# wagband_schematic.net
KiCad netlist of a schematic drawn in EAGLE
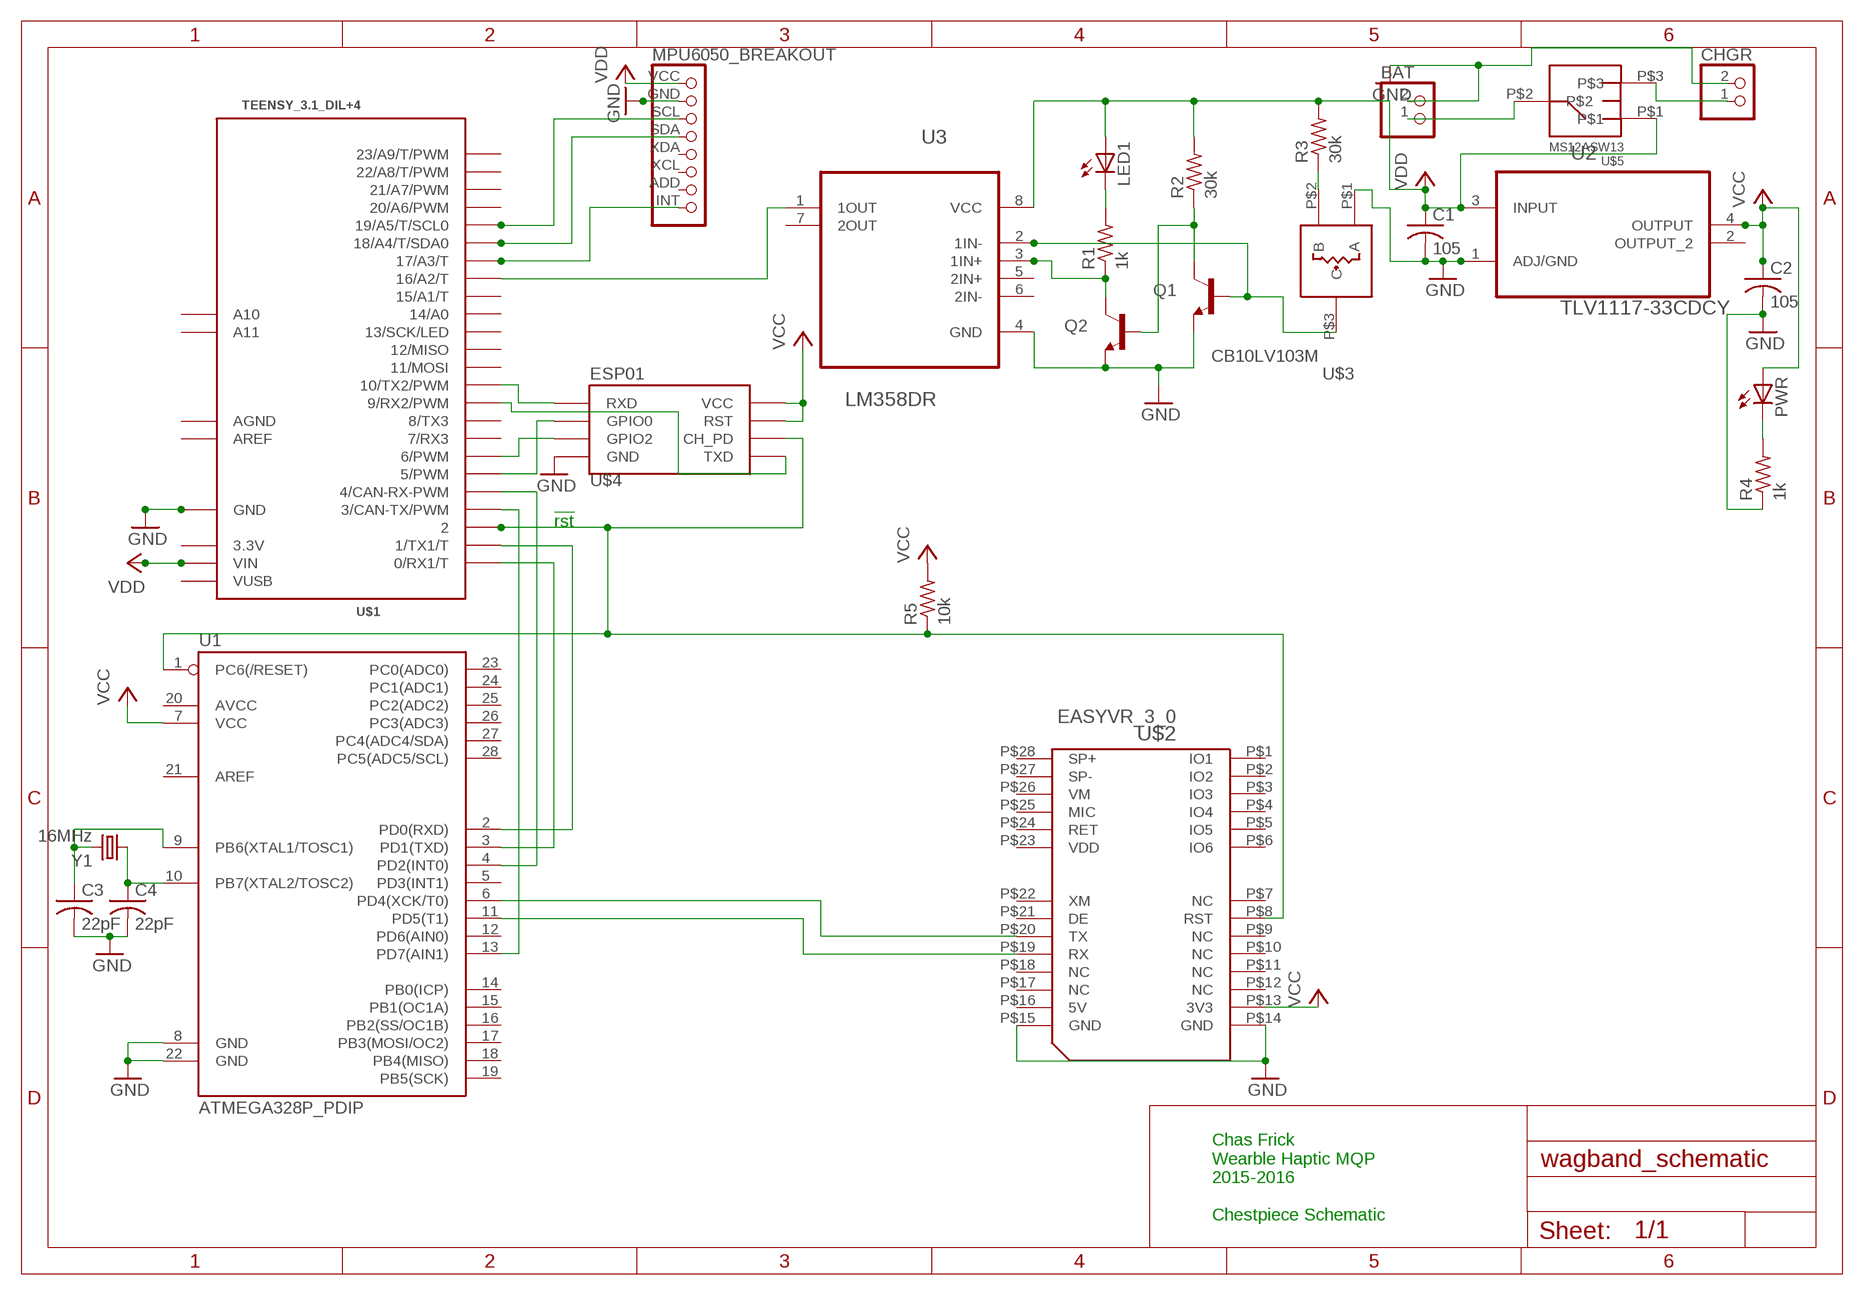
[diagram p0: schematic, sheet 1]

(export (version "E")
  (design (tool "Eeschema 10.0.6"))
  (components
    (comp (ref "BAT")
      (value "JST_2PIN-THM-RA")
      (footprint "eagle-import:JST-PH-2-THM-RA")
      (libsource (lib "eagle-import") (part "JST_2PIN-THM-RA"))
    )
    (comp (ref "C1")
      (value "105")
      (footprint "eagle-import:C0805K")
      (libsource (lib "eagle-import") (part "resistor_C-USC0805K"))
    )
    (comp (ref "C2")
      (value "105")
      (footprint "eagle-import:C0805K")
      (libsource (lib "eagle-import") (part "resistor_C-USC0805K"))
    )
    (comp (ref "C3")
      (value "22pF")
      (footprint "eagle-import:C1206K")
      (libsource (lib "eagle-import") (part "C-USC1206K"))
    )
    (comp (ref "C4")
      (value "22pF")
      (footprint "eagle-import:C1206K")
      (libsource (lib "eagle-import") (part "C-USC1206K"))
    )
    (comp (ref "CHGR")
      (value "JST_2PIN-THM-RA")
      (footprint "eagle-import:JST-PH-2-THM-RA")
      (libsource (lib "eagle-import") (part "JST_2PIN-THM-RA"))
    )
    (comp (ref "LED1")
      (value "LED5MM")
      (footprint "eagle-import:LED5MM")
      (libsource (lib "eagle-import") (part "LED5MM"))
    )
    (comp (ref "MPU6050_BREAKOUT")
      (value "MPU6050_BREAKOUT")
      (footprint "eagle-import:MPU6050")
      (libsource (lib "eagle-import") (part "MPU6050_BREAKOUT"))
    )
    (comp (ref "PWR")
      (value "LED5MM")
      (footprint "eagle-import:LED5MM")
      (libsource (lib "eagle-import") (part "LED5MM"))
    )
    (comp (ref "Q1")
      (value "TRANSISTOR_NPNMMBT3904")
      (footprint "eagle-import:SOT-23")
      (libsource (lib "eagle-import") (part "TRANSISTOR_NPNMMBT3904"))
    )
    (comp (ref "Q2")
      (value "TRANSISTOR_NPNMMBT3904")
      (footprint "eagle-import:SOT-23")
      (libsource (lib "eagle-import") (part "TRANSISTOR_NPNMMBT3904"))
    )
    (comp (ref "R1")
      (value "1k")
      (footprint "eagle-import:R1206")
      (libsource (lib "eagle-import") (part "R-US_R1206"))
    )
    (comp (ref "R2")
      (value "30k")
      (footprint "eagle-import:R1206")
      (libsource (lib "eagle-import") (part "R-US_R1206"))
    )
    (comp (ref "R3")
      (value "30k")
      (footprint "eagle-import:R1206")
      (libsource (lib "eagle-import") (part "R-US_R1206"))
    )
    (comp (ref "R4")
      (value "1k")
      (footprint "eagle-import:R1206")
      (libsource (lib "eagle-import") (part "R-US_R1206"))
    )
    (comp (ref "R5")
      (value "10k")
      (footprint "eagle-import:R1206")
      (libsource (lib "eagle-import") (part "R-US_R1206"))
    )
    (comp (ref "U$1")
      (value "TEENSY_3.1_DIL+4")
      (footprint "eagle-import:TEENSY3-DIL+4")
      (libsource (lib "eagle-import") (part "TEENSY_3.1_DIL+4"))
    )
    (comp (ref "U$2")
      (value "EASYVR_3_0")
      (footprint "eagle-import:EASYVR_3_0")
      (libsource (lib "eagle-import") (part "EASYVR_3_0"))
    )
    (comp (ref "U$3")
      (value "CB10LV103M")
      (footprint "eagle-import:CB10")
      (libsource (lib "eagle-import") (part "CB10LV103M"))
    )
    (comp (ref "U$4")
      (value "ESP01")
      (footprint "eagle-import:ESP01")
      (libsource (lib "eagle-import") (part "ESP01"))
    )
    (comp (ref "U$5")
      (value "MS12ASW13")
      (footprint "eagle-import:SPDT")
      (libsource (lib "eagle-import") (part "MS12ASW13"))
    )
    (comp (ref "U1")
      (value "ATMEGA328P_PDIP")
      (footprint "eagle-import:DIL28-3")
      (libsource (lib "eagle-import") (part "ATMEGA328P_PDIP"))
    )
    (comp (ref "U2")
      (value "TLV1117-33CDCY")
      (footprint "eagle-import:SOT230P700X180-4N")
      (libsource (lib "eagle-import") (part "TLV1117-33CDCY"))
    )
    (comp (ref "U3")
      (value "LM358DR")
      (footprint "eagle-import:SOIC127P600X175-8N")
      (libsource (lib "eagle-import") (part "LM358DR"))
    )
    (comp (ref "Y1")
      (value "16MHz")
      (footprint "eagle-import:HC49UP")
      (libsource (lib "eagle-import") (part "CRYSTALSMD"))
    )
  )
  (nets
    (net (code "1") (name "/3.3V") (class "Default")
      (node (ref "U$1") (pin "3.3V") (pinfunction "3.3V_3.3V") (pintype "power_in"))
    )
    (net (code "2") (name "/AGND") (class "Default")
      (node (ref "U$1") (pin "AGND") (pinfunction "AGND_AGND") (pintype "power_in"))
    )
    (net (code "3") (name "/AREF") (class "Default")
      (node (ref "U$1") (pin "AREF") (pinfunction "AREF_AREF") (pintype "power_in"))
    )
    (net (code "4") (name "/VUSB") (class "Default")
      (node (ref "U$1") (pin "VUSB") (pinfunction "VUSB_VUSB") (pintype "power_in"))
    )
    (net (code "5") (name "GND") (class "Default")
      (node (ref "BAT") (pin "2") (pinfunction "1_2") (pintype "passive"))
      (node (ref "C1") (pin "2") (pinfunction "2_2") (pintype "passive"))
      (node (ref "C2") (pin "2") (pinfunction "2_2") (pintype "passive"))
      (node (ref "C3") (pin "2") (pinfunction "2_2") (pintype "passive"))
      (node (ref "C4") (pin "2") (pinfunction "2_2") (pintype "passive"))
      (node (ref "CHGR") (pin "2") (pinfunction "1_2") (pintype "passive"))
      (node (ref "MPU6050_BREAKOUT") (pin "GND") (pinfunction "GND_GND") (pintype "passive"))
      (node (ref "Q1") (pin "2") (pinfunction "E_2") (pintype "passive"))
      (node (ref "Q2") (pin "2") (pinfunction "E_2") (pintype "passive"))
      (node (ref "R4") (pin "1") (pinfunction "1_1") (pintype "passive"))
      (node (ref "U$1") (pin "GND") (pinfunction "GND_GND") (pintype "power_in"))
      (node (ref "U$2") (pin "P$14") (pinfunction "GND_P$14") (pintype "power_in"))
      (node (ref "U$2") (pin "P$15") (pinfunction "GND_P$15") (pintype "power_in"))
      (node (ref "U$3") (pin "P$1") (pinfunction "A_P$1") (pintype "bidirectional"))
      (node (ref "U$4") (pin "GND") (pinfunction "GND_GND") (pintype "bidirectional"))
      (node (ref "U1") (pin "22") (pinfunction "GND_22") (pintype "bidirectional"))
      (node (ref "U1") (pin "8") (pinfunction "GND_8") (pintype "bidirectional"))
      (node (ref "U2") (pin "1") (pinfunction "ADJ/GND_1") (pintype "input"))
      (node (ref "U3") (pin "4") (pinfunction "GND_4") (pintype "passive"))
    )
    (net (code "6") (name "Net-(BAT-2)") (class "Default")
      (node (ref "BAT") (pin "1") (pinfunction "2_1") (pintype "passive"))
      (node (ref "U$5") (pin "P$2") (pinfunction "P$2_P$2") (pintype "bidirectional"))
    )
    (net (code "7") (name "Net-(CHGR-2)") (class "Default")
      (node (ref "CHGR") (pin "1") (pinfunction "2_1") (pintype "passive"))
      (node (ref "U$5") (pin "P$3") (pinfunction "P$3_P$3") (pintype "bidirectional"))
    )
    (net (code "8") (name "Net-(LED1-C)") (class "Default")
      (node (ref "LED1") (pin "K") (pinfunction "C_K") (pintype "passive"))
      (node (ref "R1") (pin "2") (pinfunction "2_2") (pintype "passive"))
    )
    (net (code "9") (name "Net-(PWR-C)") (class "Default")
      (node (ref "PWR") (pin "K") (pinfunction "C_K") (pintype "passive"))
      (node (ref "R4") (pin "2") (pinfunction "2_2") (pintype "passive"))
    )
    (net (code "10") (name "Net-(Q1-B)") (class "Default")
      (node (ref "Q1") (pin "1") (pinfunction "B_1") (pintype "passive"))
      (node (ref "U$3") (pin "P$3") (pinfunction "C_P$3") (pintype "bidirectional"))
      (node (ref "U3") (pin "2") (pinfunction "1IN-_2") (pintype "input"))
    )
    (net (code "11") (name "Net-(Q1-C)") (class "Default")
      (node (ref "Q1") (pin "3") (pinfunction "C_3") (pintype "passive"))
      (node (ref "Q2") (pin "1") (pinfunction "B_1") (pintype "passive"))
      (node (ref "R2") (pin "1") (pinfunction "1_1") (pintype "passive"))
    )
    (net (code "12") (name "Net-(Q2-C)") (class "Default")
      (node (ref "Q2") (pin "3") (pinfunction "C_3") (pintype "passive"))
      (node (ref "R1") (pin "1") (pinfunction "1_1") (pintype "passive"))
      (node (ref "U3") (pin "3") (pinfunction "1IN+_3") (pintype "input"))
    )
    (net (code "13") (name "Net-(U$1-0{slash}RX1{slash}T)") (class "Default")
      (node (ref "U$1") (pin "0") (pinfunction "0/RX1/T_0") (pintype "bidirectional"))
      (node (ref "U1") (pin "3") (pinfunction "PD1(TXD)_3") (pintype "bidirectional"))
    )
    (net (code "14") (name "Net-(U$1-1{slash}TX1{slash}T)") (class "Default")
      (node (ref "U$1") (pin "1") (pinfunction "1/TX1/T_1") (pintype "bidirectional"))
      (node (ref "U1") (pin "2") (pinfunction "PD0(RXD)_2") (pintype "bidirectional"))
    )
    (net (code "15") (name "Net-(U$1-3{slash}CAN-TX{slash}PWM)") (class "Default")
      (node (ref "U$1") (pin "3") (pinfunction "3/CAN-TX/PWM_3") (pintype "bidirectional"))
      (node (ref "U1") (pin "13") (pinfunction "PD7(AIN1)_13") (pintype "bidirectional"))
    )
    (net (code "16") (name "Net-(U$1-4{slash}CAN-RX-PWM)") (class "Default")
      (node (ref "U$1") (pin "4") (pinfunction "4/CAN-RX-PWM_4") (pintype "bidirectional"))
      (node (ref "U1") (pin "4") (pinfunction "PD2(INT0)_4") (pintype "bidirectional"))
    )
    (net (code "17") (name "Net-(U$1-5{slash}PWM)") (class "Default")
      (node (ref "U$1") (pin "5") (pinfunction "5/PWM_5") (pintype "bidirectional"))
      (node (ref "U$4") (pin "GPIO0") (pinfunction "GPIO0_GPIO0") (pintype "bidirectional"))
    )
    (net (code "18") (name "Net-(U$1-6{slash}PWM)") (class "Default")
      (node (ref "U$1") (pin "6") (pinfunction "6/PWM_6") (pintype "bidirectional"))
      (node (ref "U$4") (pin "GPIO2") (pinfunction "GPIO2_GPIO2") (pintype "bidirectional"))
    )
    (net (code "19") (name "Net-(U$1-9{slash}RX2{slash}PWM)") (class "Default")
      (node (ref "U$1") (pin "9") (pinfunction "9/RX2/PWM_9") (pintype "bidirectional"))
      (node (ref "U$4") (pin "TX") (pinfunction "TXD_TX") (pintype "bidirectional"))
    )
    (net (code "20") (name "Net-(U$1-10{slash}TX2{slash}PWM)") (class "Default")
      (node (ref "U$1") (pin "10") (pinfunction "10/TX2/PWM_10") (pintype "bidirectional"))
      (node (ref "U$4") (pin "RX") (pinfunction "RXD_RX") (pintype "bidirectional"))
    )
    (net (code "21") (name "Net-(U$1-16{slash}A2{slash}T)") (class "Default")
      (node (ref "U$1") (pin "16/A2") (pinfunction "16/A2/T_16/A2") (pintype "bidirectional"))
      (node (ref "U3") (pin "1") (pinfunction "1OUT_1") (pintype "output"))
    )
    (net (code "22") (name "Net-(U$1-17{slash}A3{slash}T)") (class "Default")
      (node (ref "MPU6050_BREAKOUT") (pin "INT") (pinfunction "INT_INT") (pintype "passive"))
      (node (ref "U$1") (pin "17/A3") (pinfunction "17/A3/T_17/A3") (pintype "bidirectional"))
    )
    (net (code "23") (name "Net-(U$1-18{slash}A4{slash}T{slash}SDA0)") (class "Default")
      (node (ref "MPU6050_BREAKOUT") (pin "SDA") (pinfunction "SDA_SDA") (pintype "passive"))
      (node (ref "U$1") (pin "18/A4") (pinfunction "18/A4/T/SDA0_18/A4") (pintype "bidirectional"))
    )
    (net (code "24") (name "Net-(U$1-19{slash}A5{slash}T{slash}SCL0)") (class "Default")
      (node (ref "MPU6050_BREAKOUT") (pin "SCL") (pinfunction "SCL_SCL") (pintype "passive"))
      (node (ref "U$1") (pin "19/A5") (pinfunction "19/A5/T/SCL0_19/A5") (pintype "bidirectional"))
    )
    (net (code "25") (name "Net-(U$2-RST)") (class "Default")
      (node (ref "R5") (pin "1") (pinfunction "1_1") (pintype "passive"))
      (node (ref "U$1") (pin "2") (pinfunction "2_2") (pintype "bidirectional"))
      (node (ref "U$2") (pin "P$8") (pinfunction "RST_P$8") (pintype "input"))
      (node (ref "U$4") (pin "CH_PD") (pinfunction "CH_PD_CH_PD") (pintype "bidirectional"))
      (node (ref "U1") (pin "1") (pinfunction "PC6(/RESET)_1") (pintype "bidirectional"))
    )
    (net (code "26") (name "Net-(U$2-RX)") (class "Default")
      (node (ref "U$2") (pin "P$19") (pinfunction "RX_P$19") (pintype "input"))
      (node (ref "U1") (pin "11") (pinfunction "PD5(T1)_11") (pintype "bidirectional"))
    )
    (net (code "27") (name "Net-(U$2-TX)") (class "Default")
      (node (ref "U$2") (pin "P$20") (pinfunction "TX_P$20") (pintype "output"))
      (node (ref "U1") (pin "6") (pinfunction "PD4(XCK/T0)_6") (pintype "bidirectional"))
    )
    (net (code "28") (name "Net-(U$3-B)") (class "Default")
      (node (ref "R3") (pin "1") (pinfunction "1_1") (pintype "passive"))
      (node (ref "U$3") (pin "P$2") (pinfunction "B_P$2") (pintype "bidirectional"))
    )
    (net (code "29") (name "Net-(U1-PB6(XTAL1{slash}TOSC1))") (class "Default")
      (node (ref "C3") (pin "1") (pinfunction "1_1") (pintype "passive"))
      (node (ref "U1") (pin "9") (pinfunction "PB6(XTAL1/TOSC1)_9") (pintype "bidirectional"))
      (node (ref "Y1") (pin "2") (pinfunction "2_2") (pintype "passive"))
    )
    (net (code "30") (name "Net-(U1-PB7(XTAL2{slash}TOSC2))") (class "Default")
      (node (ref "C4") (pin "1") (pinfunction "1_1") (pintype "passive"))
      (node (ref "U1") (pin "10") (pinfunction "PB7(XTAL2/TOSC2)_10") (pintype "bidirectional"))
      (node (ref "Y1") (pin "1") (pinfunction "1_1") (pintype "passive"))
    )
    (net (code "31") (name "VCC") (class "Default")
      (node (ref "C1") (pin "1") (pinfunction "1_1") (pintype "passive"))
      (node (ref "C2") (pin "1") (pinfunction "1_1") (pintype "passive"))
      (node (ref "LED1") (pin "A") (pinfunction "A_A") (pintype "passive"))
      (node (ref "MPU6050_BREAKOUT") (pin "VCC") (pinfunction "VCC_VCC") (pintype "passive"))
      (node (ref "PWR") (pin "A") (pinfunction "A_A") (pintype "passive"))
      (node (ref "R2") (pin "2") (pinfunction "2_2") (pintype "passive"))
      (node (ref "R3") (pin "2") (pinfunction "2_2") (pintype "passive"))
      (node (ref "R5") (pin "2") (pinfunction "2_2") (pintype "passive"))
      (node (ref "U$1") (pin "VIN") (pinfunction "VIN_VIN") (pintype "power_in"))
      (node (ref "U$2") (pin "P$13") (pinfunction "3V3_P$13") (pintype "power_in"))
      (node (ref "U$4") (pin "RST") (pinfunction "RST_RST") (pintype "bidirectional"))
      (node (ref "U$4") (pin "VCC") (pinfunction "VCC_VCC") (pintype "bidirectional"))
      (node (ref "U$5") (pin "P$1") (pinfunction "P$1_P$1") (pintype "bidirectional"))
      (node (ref "U1") (pin "7") (pinfunction "VCC_7") (pintype "bidirectional"))
      (node (ref "U2") (pin "3") (pinfunction "INPUT_3") (pintype "input"))
      (node (ref "U2") (pin "4") (pinfunction "OUTPUT_4") (pintype "output"))
      (node (ref "U3") (pin "8") (pinfunction "VCC_8") (pintype "power_in"))
    )
    (net (code "32") (name "unconnected-(MPU6050_BREAKOUT-PadADD)") (class "Default")
      (node (ref "MPU6050_BREAKOUT") (pin "ADD") (pinfunction "ADD_ADD") (pintype "passive"))
    )
    (net (code "33") (name "unconnected-(MPU6050_BREAKOUT-PadXCL)") (class "Default")
      (node (ref "MPU6050_BREAKOUT") (pin "XCL") (pinfunction "XCL_XCL") (pintype "passive"))
    )
    (net (code "34") (name "unconnected-(MPU6050_BREAKOUT-PadXDA)") (class "Default")
      (node (ref "MPU6050_BREAKOUT") (pin "XDA") (pinfunction "XDA_XDA") (pintype "passive"))
    )
    (net (code "35") (name "unconnected-(U$1-7{slash}RX3-Pad7)") (class "Default")
      (node (ref "U$1") (pin "7") (pinfunction "7/RX3_7") (pintype "bidirectional"))
    )
    (net (code "36") (name "unconnected-(U$1-8{slash}TX3-Pad8)") (class "Default")
      (node (ref "U$1") (pin "8") (pinfunction "8/TX3_8") (pintype "bidirectional"))
    )
    (net (code "37") (name "unconnected-(U$1-11{slash}MOSI-Pad11)") (class "Default")
      (node (ref "U$1") (pin "11") (pinfunction "11/MOSI_11") (pintype "bidirectional"))
    )
    (net (code "38") (name "unconnected-(U$1-12{slash}MISO-Pad12)") (class "Default")
      (node (ref "U$1") (pin "12") (pinfunction "12/MISO_12") (pintype "bidirectional"))
    )
    (net (code "39") (name "unconnected-(U$1-13{slash}SCK{slash}LED-Pad13)") (class "Default")
      (node (ref "U$1") (pin "13") (pinfunction "13/SCK/LED_13") (pintype "bidirectional"))
    )
    (net (code "40") (name "unconnected-(U$1-15{slash}A1{slash}T-Pad15{slash}A1)") (class "Default")
      (node (ref "U$1") (pin "15/A1") (pinfunction "15/A1/T_15/A1") (pintype "bidirectional"))
    )
    (net (code "41") (name "unconnected-(U$1-20{slash}A6{slash}PWM-Pad20{slash}A6)") (class "Default")
      (node (ref "U$1") (pin "20/A6") (pinfunction "20/A6/PWM_20/A6") (pintype "bidirectional"))
    )
    (net (code "42") (name "unconnected-(U$1-21{slash}A7{slash}PWM-Pad21{slash}A7)") (class "Default")
      (node (ref "U$1") (pin "21/A7") (pinfunction "21/A7/PWM_21/A7") (pintype "bidirectional"))
    )
    (net (code "43") (name "unconnected-(U$1-22{slash}A8{slash}T{slash}PWM-Pad22{slash}A8)") (class "Default")
      (node (ref "U$1") (pin "22/A8") (pinfunction "22/A8/T/PWM_22/A8") (pintype "bidirectional"))
    )
    (net (code "44") (name "unconnected-(U$1-23{slash}A9{slash}T{slash}PWM-Pad23{slash}A9)") (class "Default")
      (node (ref "U$1") (pin "23/A9") (pinfunction "23/A9/T/PWM_23/A9") (pintype "bidirectional"))
    )
    (net (code "45") (name "unconnected-(U$1-Pad14{slash}A0)") (class "Default")
      (node (ref "U$1") (pin "14/A0") (pinfunction "14/A0_14/A0") (pintype "bidirectional"))
    )
    (net (code "46") (name "unconnected-(U$1-PadA10)") (class "Default")
      (node (ref "U$1") (pin "A10") (pinfunction "A10_A10") (pintype "bidirectional"))
    )
    (net (code "47") (name "unconnected-(U$1-PadA11)") (class "Default")
      (node (ref "U$1") (pin "A11") (pinfunction "A11_A11") (pintype "bidirectional"))
    )
    (net (code "48") (name "unconnected-(U$2-5V-PadP$16)") (class "Default")
      (node (ref "U$2") (pin "P$16") (pinfunction "5V_P$16") (pintype "power_in"))
    )
    (net (code "49") (name "unconnected-(U$2-DE-PadP$21)") (class "Default")
      (node (ref "U$2") (pin "P$21") (pinfunction "DE_P$21") (pintype "bidirectional"))
    )
    (net (code "50") (name "unconnected-(U$2-IO1-PadP$1)") (class "Default")
      (node (ref "U$2") (pin "P$1") (pinfunction "IO1_P$1") (pintype "bidirectional"))
    )
    (net (code "51") (name "unconnected-(U$2-IO2-PadP$2)") (class "Default")
      (node (ref "U$2") (pin "P$2") (pinfunction "IO2_P$2") (pintype "bidirectional"))
    )
    (net (code "52") (name "unconnected-(U$2-IO3-PadP$3)") (class "Default")
      (node (ref "U$2") (pin "P$3") (pinfunction "IO3_P$3") (pintype "bidirectional"))
    )
    (net (code "53") (name "unconnected-(U$2-IO4-PadP$4)") (class "Default")
      (node (ref "U$2") (pin "P$4") (pinfunction "IO4_P$4") (pintype "bidirectional"))
    )
    (net (code "54") (name "unconnected-(U$2-IO5-PadP$5)") (class "Default")
      (node (ref "U$2") (pin "P$5") (pinfunction "IO5_P$5") (pintype "bidirectional"))
    )
    (net (code "55") (name "unconnected-(U$2-IO6-PadP$6)") (class "Default")
      (node (ref "U$2") (pin "P$6") (pinfunction "IO6_P$6") (pintype "bidirectional"))
    )
    (net (code "56") (name "unconnected-(U$2-MIC-PadP$25)") (class "Default")
      (node (ref "U$2") (pin "P$25") (pinfunction "MIC_P$25") (pintype "bidirectional"))
    )
    (net (code "57") (name "unconnected-(U$2-NC-PadP$7)") (class "Default")
      (node (ref "U$2") (pin "P$7") (pinfunction "NC_P$7") (pintype "no_connect"))
    )
    (net (code "58") (name "unconnected-(U$2-NC-PadP$9)") (class "Default")
      (node (ref "U$2") (pin "P$9") (pinfunction "NC_P$9") (pintype "no_connect"))
    )
    (net (code "59") (name "unconnected-(U$2-NC-PadP$10)") (class "Default")
      (node (ref "U$2") (pin "P$10") (pinfunction "NC_P$10") (pintype "no_connect"))
    )
    (net (code "60") (name "unconnected-(U$2-NC-PadP$11)") (class "Default")
      (node (ref "U$2") (pin "P$11") (pinfunction "NC_P$11") (pintype "no_connect"))
    )
    (net (code "61") (name "unconnected-(U$2-NC-PadP$12)") (class "Default")
      (node (ref "U$2") (pin "P$12") (pinfunction "NC_P$12") (pintype "no_connect"))
    )
    (net (code "62") (name "unconnected-(U$2-NC-PadP$17)") (class "Default")
      (node (ref "U$2") (pin "P$17") (pinfunction "NC_P$17") (pintype "no_connect"))
    )
    (net (code "63") (name "unconnected-(U$2-NC-PadP$18)") (class "Default")
      (node (ref "U$2") (pin "P$18") (pinfunction "NC_P$18") (pintype "no_connect"))
    )
    (net (code "64") (name "unconnected-(U$2-RET-PadP$24)") (class "Default")
      (node (ref "U$2") (pin "P$24") (pinfunction "RET_P$24") (pintype "bidirectional"))
    )
    (net (code "65") (name "unconnected-(U$2-SP+-PadP$28)") (class "Default")
      (node (ref "U$2") (pin "P$28") (pinfunction "SP+_P$28") (pintype "bidirectional"))
    )
    (net (code "66") (name "unconnected-(U$2-SP--PadP$27)") (class "Default")
      (node (ref "U$2") (pin "P$27") (pinfunction "SP-_P$27") (pintype "bidirectional"))
    )
    (net (code "67") (name "unconnected-(U$2-VDD-PadP$23)") (class "Default")
      (node (ref "U$2") (pin "P$23") (pinfunction "VDD_P$23") (pintype "power_in"))
    )
    (net (code "68") (name "unconnected-(U$2-VM-PadP$26)") (class "Default")
      (node (ref "U$2") (pin "P$26") (pinfunction "VM_P$26") (pintype "bidirectional"))
    )
    (net (code "69") (name "unconnected-(U$2-XM-PadP$22)") (class "Default")
      (node (ref "U$2") (pin "P$22") (pinfunction "XM_P$22") (pintype "bidirectional"))
    )
    (net (code "70") (name "unconnected-(U1-AREF-Pad21)") (class "Default")
      (node (ref "U1") (pin "21") (pinfunction "AREF_21") (pintype "bidirectional"))
    )
    (net (code "71") (name "unconnected-(U1-AVCC-Pad20)") (class "Default")
      (node (ref "U1") (pin "20") (pinfunction "AVCC_20") (pintype "bidirectional"))
    )
    (net (code "72") (name "unconnected-(U1-PB0(ICP)-Pad14)") (class "Default")
      (node (ref "U1") (pin "14") (pinfunction "PB0(ICP)_14") (pintype "bidirectional"))
    )
    (net (code "73") (name "unconnected-(U1-PB1(OC1A)-Pad15)") (class "Default")
      (node (ref "U1") (pin "15") (pinfunction "PB1(OC1A)_15") (pintype "bidirectional"))
    )
    (net (code "74") (name "unconnected-(U1-PB2(SS{slash}OC1B)-Pad16)") (class "Default")
      (node (ref "U1") (pin "16") (pinfunction "PB2(SS/OC1B)_16") (pintype "bidirectional"))
    )
    (net (code "75") (name "unconnected-(U1-PB3(MOSI{slash}OC2)-Pad17)") (class "Default")
      (node (ref "U1") (pin "17") (pinfunction "PB3(MOSI/OC2)_17") (pintype "bidirectional"))
    )
    (net (code "76") (name "unconnected-(U1-PB4(MISO)-Pad18)") (class "Default")
      (node (ref "U1") (pin "18") (pinfunction "PB4(MISO)_18") (pintype "bidirectional"))
    )
    (net (code "77") (name "unconnected-(U1-PB5(SCK)-Pad19)") (class "Default")
      (node (ref "U1") (pin "19") (pinfunction "PB5(SCK)_19") (pintype "bidirectional"))
    )
    (net (code "78") (name "unconnected-(U1-PC0(ADC0)-Pad23)") (class "Default")
      (node (ref "U1") (pin "23") (pinfunction "PC0(ADC0)_23") (pintype "bidirectional"))
    )
    (net (code "79") (name "unconnected-(U1-PC1(ADC1)-Pad24)") (class "Default")
      (node (ref "U1") (pin "24") (pinfunction "PC1(ADC1)_24") (pintype "bidirectional"))
    )
    (net (code "80") (name "unconnected-(U1-PC2(ADC2)-Pad25)") (class "Default")
      (node (ref "U1") (pin "25") (pinfunction "PC2(ADC2)_25") (pintype "bidirectional"))
    )
    (net (code "81") (name "unconnected-(U1-PC3(ADC3)-Pad26)") (class "Default")
      (node (ref "U1") (pin "26") (pinfunction "PC3(ADC3)_26") (pintype "bidirectional"))
    )
    (net (code "82") (name "unconnected-(U1-PC4(ADC4{slash}SDA)-Pad27)") (class "Default")
      (node (ref "U1") (pin "27") (pinfunction "PC4(ADC4/SDA)_27") (pintype "bidirectional"))
    )
    (net (code "83") (name "unconnected-(U1-PC5(ADC5{slash}SCL)-Pad28)") (class "Default")
      (node (ref "U1") (pin "28") (pinfunction "PC5(ADC5/SCL)_28") (pintype "bidirectional"))
    )
    (net (code "84") (name "unconnected-(U1-PD3(INT1)-Pad5)") (class "Default")
      (node (ref "U1") (pin "5") (pinfunction "PD3(INT1)_5") (pintype "bidirectional"))
    )
    (net (code "85") (name "unconnected-(U1-PD6(AIN0)-Pad12)") (class "Default")
      (node (ref "U1") (pin "12") (pinfunction "PD6(AIN0)_12") (pintype "bidirectional"))
    )
    (net (code "86") (name "unconnected-(U2-OUTPUT_2-Pad2)") (class "Default")
      (node (ref "U2") (pin "2") (pinfunction "OUTPUT_2_2") (pintype "output"))
    )
    (net (code "87") (name "unconnected-(U3-2IN+-Pad5)") (class "Default")
      (node (ref "U3") (pin "5") (pinfunction "2IN+_5") (pintype "input"))
    )
    (net (code "88") (name "unconnected-(U3-2IN--Pad6)") (class "Default")
      (node (ref "U3") (pin "6") (pinfunction "2IN-_6") (pintype "input"))
    )
    (net (code "89") (name "unconnected-(U3-2OUT-Pad7)") (class "Default")
      (node (ref "U3") (pin "7") (pinfunction "2OUT_7") (pintype "output"))
    )
  )
)
